# ledboard.net
KiCad netlist of a schematic drawn in EAGLE
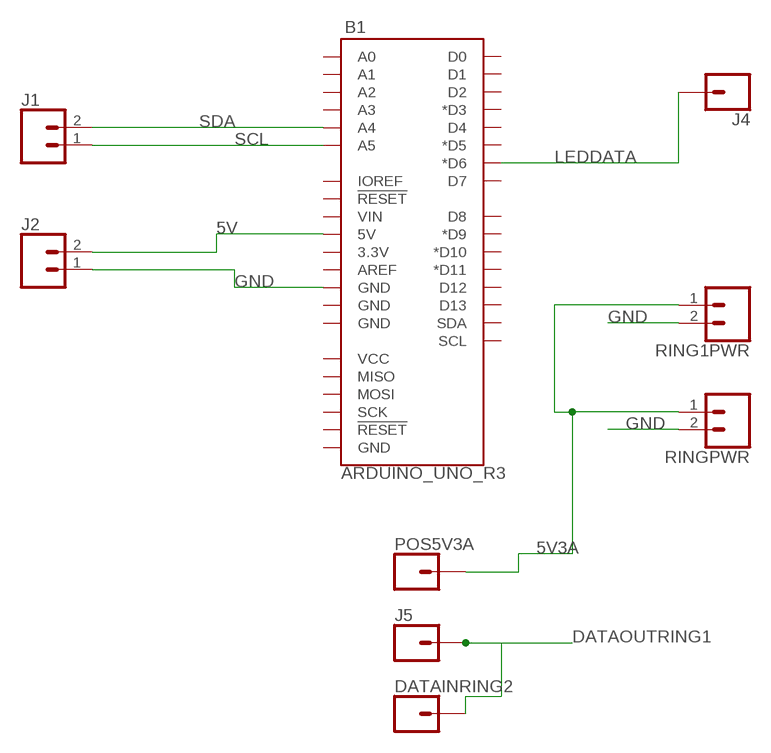
[diagram p0: schematic, sheet 1]

(export (version "E")
  (design (tool "Eeschema 10.0.6"))
  (components
    (comp (ref "B1")
      (value "ARDUINO_UNO_R3")
      (footprint "eagle-import:ARDUINO_R3")
      (libsource (lib "eagle-import") (part "ARDUINO_UNO_R3"))
    )
    (comp (ref "DATAINRING2")
      (value "CONN_01")
      (footprint "eagle-import:1X01")
      (libsource (lib "eagle-import") (part "CONN_01"))
    )
    (comp (ref "J1")
      (value "CONN_023.5MM")
      (footprint "eagle-import:SCREWTERMINAL-3.5MM-2")
      (libsource (lib "eagle-import") (part "CONN_023.5MM"))
    )
    (comp (ref "J2")
      (value "CONN_023.5MM")
      (footprint "eagle-import:SCREWTERMINAL-3.5MM-2")
      (libsource (lib "eagle-import") (part "CONN_023.5MM"))
    )
    (comp (ref "J4")
      (value "CONN_01")
      (footprint "eagle-import:1X01")
      (libsource (lib "eagle-import") (part "CONN_01"))
    )
    (comp (ref "J5")
      (value "CONN_01")
      (footprint "eagle-import:1X01")
      (libsource (lib "eagle-import") (part "CONN_01"))
    )
    (comp (ref "POS5V3A")
      (value "CONN_01")
      (footprint "eagle-import:1X01")
      (libsource (lib "eagle-import") (part "CONN_01"))
    )
    (comp (ref "RING1PWR")
      (value "CONN_023.5MM")
      (footprint "eagle-import:SCREWTERMINAL-3.5MM-2")
      (libsource (lib "eagle-import") (part "CONN_023.5MM"))
    )
    (comp (ref "RINGPWR")
      (value "CONN_023.5MM")
      (footprint "eagle-import:SCREWTERMINAL-3.5MM-2")
      (libsource (lib "eagle-import") (part "CONN_023.5MM"))
    )
  )
  (nets
    (net (code "1") (name "/5V") (class "Default")
      (node (ref "B1") (pin "5V") (pinfunction "5V_5V") (pintype "bidirectional"))
      (node (ref "J2") (pin "2") (pinfunction "2_2") (pintype "passive"))
    )
    (net (code "2") (name "/5V3A") (class "Default")
      (node (ref "POS5V3A") (pin "1") (pinfunction "1_1") (pintype "passive"))
      (node (ref "RING1PWR") (pin "1") (pinfunction "1_1") (pintype "passive"))
      (node (ref "RINGPWR") (pin "1") (pinfunction "1_1") (pintype "passive"))
    )
    (net (code "3") (name "/DATAOUTRING1") (class "Default")
      (node (ref "DATAINRING2") (pin "1") (pinfunction "1_1") (pintype "passive"))
      (node (ref "J5") (pin "1") (pinfunction "1_1") (pintype "passive"))
    )
    (net (code "4") (name "/GND") (class "Default")
      (node (ref "B1") (pin "GND@4") (pinfunction "GND_GND@4") (pintype "bidirectional"))
      (node (ref "J2") (pin "1") (pinfunction "1_1") (pintype "passive"))
      (node (ref "RING1PWR") (pin "2") (pinfunction "2_2") (pintype "passive"))
      (node (ref "RINGPWR") (pin "2") (pinfunction "2_2") (pintype "passive"))
    )
    (net (code "5") (name "/LEDDATA") (class "Default")
      (node (ref "B1") (pin "D6") (pinfunction "*D6_D6") (pintype "bidirectional"))
      (node (ref "J4") (pin "1") (pinfunction "1_1") (pintype "passive"))
    )
    (net (code "6") (name "/SCL") (class "Default")
      (node (ref "B1") (pin "A5") (pinfunction "A5_A5") (pintype "bidirectional"))
      (node (ref "J1") (pin "1") (pinfunction "1_1") (pintype "passive"))
    )
    (net (code "7") (name "/SDA") (class "Default")
      (node (ref "B1") (pin "A4") (pinfunction "A4_A4") (pintype "bidirectional"))
      (node (ref "J1") (pin "2") (pinfunction "2_2") (pintype "passive"))
    )
    (net (code "8") (name "unconnected-(B1-*D3-PadD3)") (class "Default")
      (node (ref "B1") (pin "D3") (pinfunction "*D3_D3") (pintype "bidirectional"))
    )
    (net (code "9") (name "unconnected-(B1-*D5-PadD5)") (class "Default")
      (node (ref "B1") (pin "D5") (pinfunction "*D5_D5") (pintype "bidirectional"))
    )
    (net (code "10") (name "unconnected-(B1-*D9-PadD9)") (class "Default")
      (node (ref "B1") (pin "D9") (pinfunction "*D9_D9") (pintype "bidirectional"))
    )
    (net (code "11") (name "unconnected-(B1-*D10-PadD10)") (class "Default")
      (node (ref "B1") (pin "D10") (pinfunction "*D10_D10") (pintype "bidirectional"))
    )
    (net (code "12") (name "unconnected-(B1-*D11-PadD11)") (class "Default")
      (node (ref "B1") (pin "D11") (pinfunction "*D11_D11") (pintype "bidirectional"))
    )
    (net (code "13") (name "unconnected-(B1-GND-PadGND@1)") (class "Default")
      (node (ref "B1") (pin "GND@1") (pinfunction "GND_GND@1") (pintype "bidirectional"))
    )
    (net (code "14") (name "unconnected-(B1-GND-PadGND@2)") (class "Default")
      (node (ref "B1") (pin "GND@2") (pinfunction "GND_GND@2") (pintype "bidirectional"))
    )
    (net (code "15") (name "unconnected-(B1-GND-PadGND@3)") (class "Default")
      (node (ref "B1") (pin "GND@3") (pinfunction "GND_GND@3") (pintype "bidirectional"))
    )
    (net (code "16") (name "unconnected-(B1-Pad3.3V)") (class "Default")
      (node (ref "B1") (pin "3.3V") (pinfunction "3.3V_3.3V") (pintype "bidirectional"))
    )
    (net (code "17") (name "unconnected-(B1-PadA0)") (class "Default")
      (node (ref "B1") (pin "A0") (pinfunction "A0_A0") (pintype "bidirectional"))
    )
    (net (code "18") (name "unconnected-(B1-PadA1)") (class "Default")
      (node (ref "B1") (pin "A1") (pinfunction "A1_A1") (pintype "bidirectional"))
    )
    (net (code "19") (name "unconnected-(B1-PadA2)") (class "Default")
      (node (ref "B1") (pin "A2") (pinfunction "A2_A2") (pintype "bidirectional"))
    )
    (net (code "20") (name "unconnected-(B1-PadA3)") (class "Default")
      (node (ref "B1") (pin "A3") (pinfunction "A3_A3") (pintype "bidirectional"))
    )
    (net (code "21") (name "unconnected-(B1-PadAREF)") (class "Default")
      (node (ref "B1") (pin "AREF") (pinfunction "AREF_AREF") (pintype "bidirectional"))
    )
    (net (code "22") (name "unconnected-(B1-PadD0)") (class "Default")
      (node (ref "B1") (pin "D0") (pinfunction "D0_D0") (pintype "bidirectional"))
    )
    (net (code "23") (name "unconnected-(B1-PadD1)") (class "Default")
      (node (ref "B1") (pin "D1") (pinfunction "D1_D1") (pintype "bidirectional"))
    )
    (net (code "24") (name "unconnected-(B1-PadD2)") (class "Default")
      (node (ref "B1") (pin "D2") (pinfunction "D2_D2") (pintype "bidirectional"))
    )
    (net (code "25") (name "unconnected-(B1-PadD4)") (class "Default")
      (node (ref "B1") (pin "D4") (pinfunction "D4_D4") (pintype "bidirectional"))
    )
    (net (code "26") (name "unconnected-(B1-PadD7)") (class "Default")
      (node (ref "B1") (pin "D7") (pinfunction "D7_D7") (pintype "bidirectional"))
    )
    (net (code "27") (name "unconnected-(B1-PadD8)") (class "Default")
      (node (ref "B1") (pin "D8") (pinfunction "D8_D8") (pintype "bidirectional"))
    )
    (net (code "28") (name "unconnected-(B1-PadD12)") (class "Default")
      (node (ref "B1") (pin "D12") (pinfunction "D12_D12") (pintype "bidirectional"))
    )
    (net (code "29") (name "unconnected-(B1-PadD13)") (class "Default")
      (node (ref "B1") (pin "D13") (pinfunction "D13_D13") (pintype "bidirectional"))
    )
    (net (code "30") (name "unconnected-(B1-PadIOREF)") (class "Default")
      (node (ref "B1") (pin "IOREF") (pinfunction "IOREF_IOREF") (pintype "bidirectional"))
    )
    (net (code "31") (name "unconnected-(B1-PadMISO)") (class "Default")
      (node (ref "B1") (pin "MISO") (pinfunction "MISO_MISO") (pintype "bidirectional"))
    )
    (net (code "32") (name "unconnected-(B1-PadMOSI)") (class "Default")
      (node (ref "B1") (pin "MOSI") (pinfunction "MOSI_MOSI") (pintype "bidirectional"))
    )
    (net (code "33") (name "unconnected-(B1-PadSCK)") (class "Default")
      (node (ref "B1") (pin "SCK") (pinfunction "SCK_SCK") (pintype "bidirectional"))
    )
    (net (code "34") (name "unconnected-(B1-PadSCL)") (class "Default")
      (node (ref "B1") (pin "SCL") (pinfunction "SCL_SCL") (pintype "bidirectional"))
    )
    (net (code "35") (name "unconnected-(B1-PadSDA)") (class "Default")
      (node (ref "B1") (pin "SDA") (pinfunction "SDA_SDA") (pintype "bidirectional"))
    )
    (net (code "36") (name "unconnected-(B1-PadVCC)") (class "Default")
      (node (ref "B1") (pin "VCC") (pinfunction "VCC_VCC") (pintype "bidirectional"))
    )
    (net (code "37") (name "unconnected-(B1-PadVIN)") (class "Default")
      (node (ref "B1") (pin "VIN") (pinfunction "VIN_VIN") (pintype "bidirectional"))
    )
    (net (code "38") (name "unconnected-(B1-~{RESET}-PadRESET@1)") (class "Default")
      (node (ref "B1") (pin "RESET@1") (pinfunction "~{RESET}_RESET@1") (pintype "bidirectional"))
    )
    (net (code "39") (name "unconnected-(B1-~{RESET}-PadRESET@2)") (class "Default")
      (node (ref "B1") (pin "RESET@2") (pinfunction "~{RESET}_RESET@2") (pintype "bidirectional"))
    )
  )
)
